# ruralhack-board.net
KiCad netlist of a schematic drawn in EAGLE
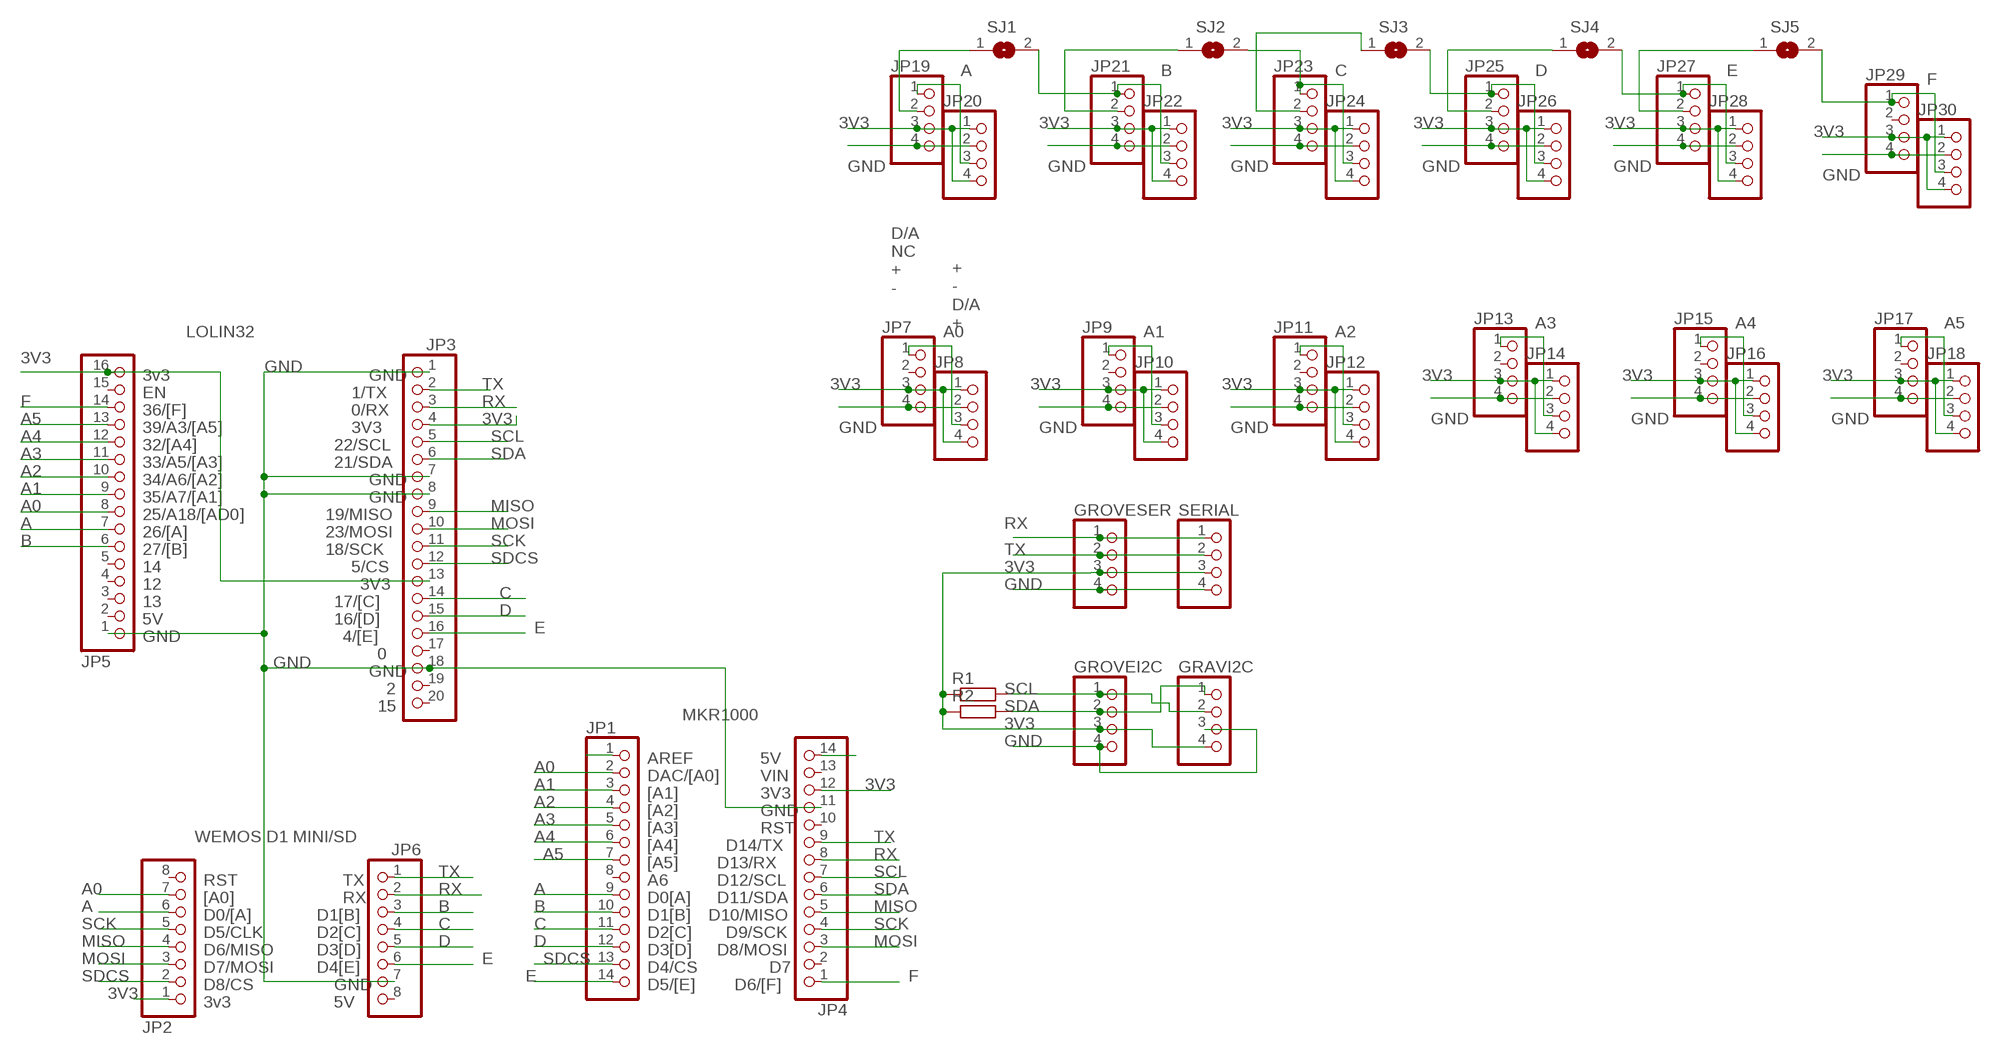
[diagram p0: schematic, sheet 1]

(export (version "E")
  (design (tool "Eeschema 10.0.6"))
  (components
    (comp (ref "GRAVI2C")
      (value "PINHD-1X4")
      (footprint "eagle-import:1X04")
      (libsource (lib "eagle-import") (part "PINHD-1X4"))
    )
    (comp (ref "GROVEI2C")
      (value "PINHD-1X4")
      (footprint "eagle-import:1X04")
      (libsource (lib "eagle-import") (part "PINHD-1X4"))
    )
    (comp (ref "GROVESER")
      (value "PINHD-1X4")
      (footprint "eagle-import:1X04")
      (libsource (lib "eagle-import") (part "PINHD-1X4"))
    )
    (comp (ref "JP1")
      (value "PINHD-1X14")
      (footprint "eagle-import:1X14")
      (libsource (lib "eagle-import") (part "PINHD-1X14"))
    )
    (comp (ref "JP2")
      (value "PINHD-1X8")
      (footprint "eagle-import:1X08")
      (libsource (lib "eagle-import") (part "PINHD-1X8"))
    )
    (comp (ref "JP3")
      (value "PINHD-1X20")
      (footprint "eagle-import:1X20")
      (libsource (lib "eagle-import") (part "PINHD-1X20"))
    )
    (comp (ref "JP4")
      (value "PINHD-1X14")
      (footprint "eagle-import:1X14")
      (libsource (lib "eagle-import") (part "PINHD-1X14"))
    )
    (comp (ref "JP5")
      (value "PINHD-1X16")
      (footprint "eagle-import:1X16")
      (libsource (lib "eagle-import") (part "PINHD-1X16"))
    )
    (comp (ref "JP6")
      (value "PINHD-1X8")
      (footprint "eagle-import:1X08")
      (libsource (lib "eagle-import") (part "PINHD-1X8"))
    )
    (comp (ref "JP7")
      (value "PINHD-1X4")
      (footprint "eagle-import:1X04")
      (libsource (lib "eagle-import") (part "PINHD-1X4"))
    )
    (comp (ref "JP8")
      (value "PINHD-1X4")
      (footprint "eagle-import:1X04")
      (libsource (lib "eagle-import") (part "PINHD-1X4"))
    )
    (comp (ref "JP9")
      (value "PINHD-1X4")
      (footprint "eagle-import:1X04")
      (libsource (lib "eagle-import") (part "PINHD-1X4"))
    )
    (comp (ref "JP10")
      (value "PINHD-1X4")
      (footprint "eagle-import:1X04")
      (libsource (lib "eagle-import") (part "PINHD-1X4"))
    )
    (comp (ref "JP11")
      (value "PINHD-1X4")
      (footprint "eagle-import:1X04")
      (libsource (lib "eagle-import") (part "PINHD-1X4"))
    )
    (comp (ref "JP12")
      (value "PINHD-1X4")
      (footprint "eagle-import:1X04")
      (libsource (lib "eagle-import") (part "PINHD-1X4"))
    )
    (comp (ref "JP13")
      (value "PINHD-1X4")
      (footprint "eagle-import:1X04")
      (libsource (lib "eagle-import") (part "PINHD-1X4"))
    )
    (comp (ref "JP14")
      (value "PINHD-1X4")
      (footprint "eagle-import:1X04")
      (libsource (lib "eagle-import") (part "PINHD-1X4"))
    )
    (comp (ref "JP15")
      (value "PINHD-1X4")
      (footprint "eagle-import:1X04")
      (libsource (lib "eagle-import") (part "PINHD-1X4"))
    )
    (comp (ref "JP16")
      (value "PINHD-1X4")
      (footprint "eagle-import:1X04")
      (libsource (lib "eagle-import") (part "PINHD-1X4"))
    )
    (comp (ref "JP17")
      (value "PINHD-1X4")
      (footprint "eagle-import:1X04")
      (libsource (lib "eagle-import") (part "PINHD-1X4"))
    )
    (comp (ref "JP18")
      (value "PINHD-1X4")
      (footprint "eagle-import:1X04")
      (libsource (lib "eagle-import") (part "PINHD-1X4"))
    )
    (comp (ref "JP19")
      (value "PINHD-1X4")
      (footprint "eagle-import:1X04")
      (libsource (lib "eagle-import") (part "PINHD-1X4"))
    )
    (comp (ref "JP20")
      (value "PINHD-1X4")
      (footprint "eagle-import:1X04")
      (libsource (lib "eagle-import") (part "PINHD-1X4"))
    )
    (comp (ref "JP21")
      (value "PINHD-1X4")
      (footprint "eagle-import:1X04")
      (libsource (lib "eagle-import") (part "PINHD-1X4"))
    )
    (comp (ref "JP22")
      (value "PINHD-1X4")
      (footprint "eagle-import:1X04")
      (libsource (lib "eagle-import") (part "PINHD-1X4"))
    )
    (comp (ref "JP23")
      (value "PINHD-1X4")
      (footprint "eagle-import:1X04")
      (libsource (lib "eagle-import") (part "PINHD-1X4"))
    )
    (comp (ref "JP24")
      (value "PINHD-1X4")
      (footprint "eagle-import:1X04")
      (libsource (lib "eagle-import") (part "PINHD-1X4"))
    )
    (comp (ref "JP25")
      (value "PINHD-1X4")
      (footprint "eagle-import:1X04")
      (libsource (lib "eagle-import") (part "PINHD-1X4"))
    )
    (comp (ref "JP26")
      (value "PINHD-1X4")
      (footprint "eagle-import:1X04")
      (libsource (lib "eagle-import") (part "PINHD-1X4"))
    )
    (comp (ref "JP27")
      (value "PINHD-1X4")
      (footprint "eagle-import:1X04")
      (libsource (lib "eagle-import") (part "PINHD-1X4"))
    )
    (comp (ref "JP28")
      (value "PINHD-1X4")
      (footprint "eagle-import:1X04")
      (libsource (lib "eagle-import") (part "PINHD-1X4"))
    )
    (comp (ref "JP29")
      (value "PINHD-1X4")
      (footprint "eagle-import:1X04")
      (libsource (lib "eagle-import") (part "PINHD-1X4"))
    )
    (comp (ref "JP30")
      (value "PINHD-1X4")
      (footprint "eagle-import:1X04")
      (libsource (lib "eagle-import") (part "PINHD-1X4"))
    )
    (comp (ref "R1")
      (value "R-EU_0204/7")
      (footprint "eagle-import:0204_7")
      (libsource (lib "eagle-import") (part "R-EU_0204/7"))
    )
    (comp (ref "R2")
      (value "R-EU_0204/7")
      (footprint "eagle-import:0204_7")
      (libsource (lib "eagle-import") (part "R-EU_0204/7"))
    )
    (comp (ref "SERIAL")
      (value "PINHD-1X4")
      (footprint "eagle-import:1X04")
      (libsource (lib "eagle-import") (part "PINHD-1X4"))
    )
    (comp (ref "SJ1")
      (value "SJW")
      (footprint "eagle-import:SJW")
      (libsource (lib "eagle-import") (part "SJW"))
    )
    (comp (ref "SJ2")
      (value "SJW")
      (footprint "eagle-import:SJW")
      (libsource (lib "eagle-import") (part "SJW"))
    )
    (comp (ref "SJ3")
      (value "SJW")
      (footprint "eagle-import:SJW")
      (libsource (lib "eagle-import") (part "SJW"))
    )
    (comp (ref "SJ4")
      (value "SJW")
      (footprint "eagle-import:SJW")
      (libsource (lib "eagle-import") (part "SJW"))
    )
    (comp (ref "SJ5")
      (value "SJW")
      (footprint "eagle-import:SJW")
      (libsource (lib "eagle-import") (part "SJW"))
    )
  )
  (nets
    (net (code "1") (name "/3V3") (class "Default")
      (node (ref "GRAVI2C") (pin "4") (pinfunction "4_4") (pintype "passive"))
      (node (ref "GROVEI2C") (pin "3") (pinfunction "3_3") (pintype "passive"))
      (node (ref "GROVESER") (pin "3") (pinfunction "3_3") (pintype "passive"))
      (node (ref "JP10") (pin "1") (pinfunction "1_1") (pintype "passive"))
      (node (ref "JP10") (pin "4") (pinfunction "4_4") (pintype "passive"))
      (node (ref "JP11") (pin "3") (pinfunction "3_3") (pintype "passive"))
      (node (ref "JP12") (pin "1") (pinfunction "1_1") (pintype "passive"))
      (node (ref "JP12") (pin "4") (pinfunction "4_4") (pintype "passive"))
      (node (ref "JP13") (pin "3") (pinfunction "3_3") (pintype "passive"))
      (node (ref "JP14") (pin "1") (pinfunction "1_1") (pintype "passive"))
      (node (ref "JP14") (pin "4") (pinfunction "4_4") (pintype "passive"))
      (node (ref "JP15") (pin "3") (pinfunction "3_3") (pintype "passive"))
      (node (ref "JP16") (pin "1") (pinfunction "1_1") (pintype "passive"))
      (node (ref "JP16") (pin "4") (pinfunction "4_4") (pintype "passive"))
      (node (ref "JP17") (pin "3") (pinfunction "3_3") (pintype "passive"))
      (node (ref "JP18") (pin "1") (pinfunction "1_1") (pintype "passive"))
      (node (ref "JP18") (pin "4") (pinfunction "4_4") (pintype "passive"))
      (node (ref "JP19") (pin "3") (pinfunction "3_3") (pintype "passive"))
      (node (ref "JP2") (pin "1") (pinfunction "1_1") (pintype "passive"))
      (node (ref "JP20") (pin "1") (pinfunction "1_1") (pintype "passive"))
      (node (ref "JP20") (pin "4") (pinfunction "4_4") (pintype "passive"))
      (node (ref "JP21") (pin "3") (pinfunction "3_3") (pintype "passive"))
      (node (ref "JP22") (pin "1") (pinfunction "1_1") (pintype "passive"))
      (node (ref "JP22") (pin "4") (pinfunction "4_4") (pintype "passive"))
      (node (ref "JP23") (pin "3") (pinfunction "3_3") (pintype "passive"))
      (node (ref "JP24") (pin "1") (pinfunction "1_1") (pintype "passive"))
      (node (ref "JP24") (pin "4") (pinfunction "4_4") (pintype "passive"))
      (node (ref "JP25") (pin "3") (pinfunction "3_3") (pintype "passive"))
      (node (ref "JP26") (pin "1") (pinfunction "1_1") (pintype "passive"))
      (node (ref "JP26") (pin "4") (pinfunction "4_4") (pintype "passive"))
      (node (ref "JP27") (pin "3") (pinfunction "3_3") (pintype "passive"))
      (node (ref "JP28") (pin "1") (pinfunction "1_1") (pintype "passive"))
      (node (ref "JP28") (pin "4") (pinfunction "4_4") (pintype "passive"))
      (node (ref "JP29") (pin "3") (pinfunction "3_3") (pintype "passive"))
      (node (ref "JP3") (pin "13") (pinfunction "13_13") (pintype "passive"))
      (node (ref "JP3") (pin "4") (pinfunction "4_4") (pintype "passive"))
      (node (ref "JP30") (pin "1") (pinfunction "1_1") (pintype "passive"))
      (node (ref "JP30") (pin "4") (pinfunction "4_4") (pintype "passive"))
      (node (ref "JP4") (pin "12") (pinfunction "12_12") (pintype "passive"))
      (node (ref "JP5") (pin "16") (pinfunction "16_16") (pintype "passive"))
      (node (ref "JP7") (pin "3") (pinfunction "3_3") (pintype "passive"))
      (node (ref "JP8") (pin "1") (pinfunction "1_1") (pintype "passive"))
      (node (ref "JP8") (pin "4") (pinfunction "4_4") (pintype "passive"))
      (node (ref "JP9") (pin "3") (pinfunction "3_3") (pintype "passive"))
      (node (ref "R1") (pin "1") (pinfunction "1_1") (pintype "passive"))
      (node (ref "R2") (pin "1") (pinfunction "1_1") (pintype "passive"))
      (node (ref "SERIAL") (pin "3") (pinfunction "3_3") (pintype "passive"))
    )
    (net (code "2") (name "/A") (class "Default")
      (node (ref "JP1") (pin "9") (pinfunction "9_9") (pintype "passive"))
      (node (ref "JP19") (pin "1") (pinfunction "1_1") (pintype "passive"))
      (node (ref "JP2") (pin "6") (pinfunction "6_6") (pintype "passive"))
      (node (ref "JP20") (pin "3") (pinfunction "3_3") (pintype "passive"))
      (node (ref "JP5") (pin "7") (pinfunction "7_7") (pintype "passive"))
    )
    (net (code "3") (name "/A0") (class "Default")
      (node (ref "JP1") (pin "2") (pinfunction "2_2") (pintype "passive"))
      (node (ref "JP2") (pin "7") (pinfunction "7_7") (pintype "passive"))
      (node (ref "JP5") (pin "8") (pinfunction "8_8") (pintype "passive"))
      (node (ref "JP7") (pin "1") (pinfunction "1_1") (pintype "passive"))
      (node (ref "JP8") (pin "3") (pinfunction "3_3") (pintype "passive"))
    )
    (net (code "4") (name "/A1") (class "Default")
      (node (ref "JP1") (pin "3") (pinfunction "3_3") (pintype "passive"))
      (node (ref "JP10") (pin "3") (pinfunction "3_3") (pintype "passive"))
      (node (ref "JP5") (pin "9") (pinfunction "9_9") (pintype "passive"))
      (node (ref "JP9") (pin "1") (pinfunction "1_1") (pintype "passive"))
    )
    (net (code "5") (name "/A2") (class "Default")
      (node (ref "JP1") (pin "4") (pinfunction "4_4") (pintype "passive"))
      (node (ref "JP11") (pin "1") (pinfunction "1_1") (pintype "passive"))
      (node (ref "JP12") (pin "3") (pinfunction "3_3") (pintype "passive"))
      (node (ref "JP5") (pin "10") (pinfunction "10_10") (pintype "passive"))
    )
    (net (code "6") (name "/A3") (class "Default")
      (node (ref "JP1") (pin "5") (pinfunction "5_5") (pintype "passive"))
      (node (ref "JP13") (pin "1") (pinfunction "1_1") (pintype "passive"))
      (node (ref "JP14") (pin "3") (pinfunction "3_3") (pintype "passive"))
      (node (ref "JP5") (pin "11") (pinfunction "11_11") (pintype "passive"))
    )
    (net (code "7") (name "/A4") (class "Default")
      (node (ref "JP1") (pin "6") (pinfunction "6_6") (pintype "passive"))
      (node (ref "JP15") (pin "1") (pinfunction "1_1") (pintype "passive"))
      (node (ref "JP16") (pin "3") (pinfunction "3_3") (pintype "passive"))
      (node (ref "JP5") (pin "12") (pinfunction "12_12") (pintype "passive"))
    )
    (net (code "8") (name "/A5") (class "Default")
      (node (ref "JP1") (pin "7") (pinfunction "7_7") (pintype "passive"))
      (node (ref "JP17") (pin "1") (pinfunction "1_1") (pintype "passive"))
      (node (ref "JP18") (pin "3") (pinfunction "3_3") (pintype "passive"))
      (node (ref "JP5") (pin "13") (pinfunction "13_13") (pintype "passive"))
    )
    (net (code "9") (name "/B") (class "Default")
      (node (ref "JP1") (pin "10") (pinfunction "10_10") (pintype "passive"))
      (node (ref "JP21") (pin "1") (pinfunction "1_1") (pintype "passive"))
      (node (ref "JP22") (pin "3") (pinfunction "3_3") (pintype "passive"))
      (node (ref "JP5") (pin "6") (pinfunction "6_6") (pintype "passive"))
      (node (ref "JP6") (pin "3") (pinfunction "3_3") (pintype "passive"))
      (node (ref "SJ1") (pin "2") (pinfunction "2_2") (pintype "passive"))
    )
    (net (code "10") (name "/C") (class "Default")
      (node (ref "JP1") (pin "11") (pinfunction "11_11") (pintype "passive"))
      (node (ref "JP23") (pin "1") (pinfunction "1_1") (pintype "passive"))
      (node (ref "JP24") (pin "3") (pinfunction "3_3") (pintype "passive"))
      (node (ref "JP3") (pin "14") (pinfunction "14_14") (pintype "passive"))
      (node (ref "JP6") (pin "4") (pinfunction "4_4") (pintype "passive"))
      (node (ref "SJ2") (pin "2") (pinfunction "2_2") (pintype "passive"))
    )
    (net (code "11") (name "/D") (class "Default")
      (node (ref "JP1") (pin "12") (pinfunction "12_12") (pintype "passive"))
      (node (ref "JP25") (pin "1") (pinfunction "1_1") (pintype "passive"))
      (node (ref "JP26") (pin "3") (pinfunction "3_3") (pintype "passive"))
      (node (ref "JP3") (pin "15") (pinfunction "15_15") (pintype "passive"))
      (node (ref "JP6") (pin "5") (pinfunction "5_5") (pintype "passive"))
      (node (ref "SJ3") (pin "2") (pinfunction "2_2") (pintype "passive"))
    )
    (net (code "12") (name "/E") (class "Default")
      (node (ref "JP1") (pin "14") (pinfunction "14_14") (pintype "passive"))
      (node (ref "JP27") (pin "1") (pinfunction "1_1") (pintype "passive"))
      (node (ref "JP28") (pin "3") (pinfunction "3_3") (pintype "passive"))
      (node (ref "JP3") (pin "16") (pinfunction "16_16") (pintype "passive"))
      (node (ref "JP6") (pin "6") (pinfunction "6_6") (pintype "passive"))
      (node (ref "SJ4") (pin "2") (pinfunction "2_2") (pintype "passive"))
    )
    (net (code "13") (name "/F") (class "Default")
      (node (ref "JP29") (pin "1") (pinfunction "1_1") (pintype "passive"))
      (node (ref "JP30") (pin "3") (pinfunction "3_3") (pintype "passive"))
      (node (ref "JP4") (pin "1") (pinfunction "1_1") (pintype "passive"))
      (node (ref "JP5") (pin "14") (pinfunction "14_14") (pintype "passive"))
      (node (ref "SJ5") (pin "2") (pinfunction "2_2") (pintype "passive"))
    )
    (net (code "14") (name "/GND") (class "Default")
      (node (ref "GRAVI2C") (pin "3") (pinfunction "3_3") (pintype "passive"))
      (node (ref "GROVEI2C") (pin "4") (pinfunction "4_4") (pintype "passive"))
      (node (ref "GROVESER") (pin "4") (pinfunction "4_4") (pintype "passive"))
      (node (ref "JP10") (pin "2") (pinfunction "2_2") (pintype "passive"))
      (node (ref "JP11") (pin "4") (pinfunction "4_4") (pintype "passive"))
      (node (ref "JP12") (pin "2") (pinfunction "2_2") (pintype "passive"))
      (node (ref "JP13") (pin "4") (pinfunction "4_4") (pintype "passive"))
      (node (ref "JP14") (pin "2") (pinfunction "2_2") (pintype "passive"))
      (node (ref "JP15") (pin "4") (pinfunction "4_4") (pintype "passive"))
      (node (ref "JP16") (pin "2") (pinfunction "2_2") (pintype "passive"))
      (node (ref "JP17") (pin "4") (pinfunction "4_4") (pintype "passive"))
      (node (ref "JP18") (pin "2") (pinfunction "2_2") (pintype "passive"))
      (node (ref "JP19") (pin "4") (pinfunction "4_4") (pintype "passive"))
      (node (ref "JP20") (pin "2") (pinfunction "2_2") (pintype "passive"))
      (node (ref "JP21") (pin "4") (pinfunction "4_4") (pintype "passive"))
      (node (ref "JP22") (pin "2") (pinfunction "2_2") (pintype "passive"))
      (node (ref "JP23") (pin "4") (pinfunction "4_4") (pintype "passive"))
      (node (ref "JP24") (pin "2") (pinfunction "2_2") (pintype "passive"))
      (node (ref "JP25") (pin "4") (pinfunction "4_4") (pintype "passive"))
      (node (ref "JP26") (pin "2") (pinfunction "2_2") (pintype "passive"))
      (node (ref "JP27") (pin "4") (pinfunction "4_4") (pintype "passive"))
      (node (ref "JP28") (pin "2") (pinfunction "2_2") (pintype "passive"))
      (node (ref "JP29") (pin "4") (pinfunction "4_4") (pintype "passive"))
      (node (ref "JP3") (pin "1") (pinfunction "1_1") (pintype "passive"))
      (node (ref "JP3") (pin "18") (pinfunction "18_18") (pintype "passive"))
      (node (ref "JP3") (pin "7") (pinfunction "7_7") (pintype "passive"))
      (node (ref "JP3") (pin "8") (pinfunction "8_8") (pintype "passive"))
      (node (ref "JP30") (pin "2") (pinfunction "2_2") (pintype "passive"))
      (node (ref "JP4") (pin "11") (pinfunction "11_11") (pintype "passive"))
      (node (ref "JP5") (pin "1") (pinfunction "1_1") (pintype "passive"))
      (node (ref "JP6") (pin "7") (pinfunction "7_7") (pintype "passive"))
      (node (ref "JP7") (pin "4") (pinfunction "4_4") (pintype "passive"))
      (node (ref "JP8") (pin "2") (pinfunction "2_2") (pintype "passive"))
      (node (ref "JP9") (pin "4") (pinfunction "4_4") (pintype "passive"))
      (node (ref "SERIAL") (pin "4") (pinfunction "4_4") (pintype "passive"))
    )
    (net (code "15") (name "/MISO") (class "Default")
      (node (ref "JP2") (pin "4") (pinfunction "4_4") (pintype "passive"))
      (node (ref "JP3") (pin "9") (pinfunction "9_9") (pintype "passive"))
      (node (ref "JP4") (pin "5") (pinfunction "5_5") (pintype "passive"))
    )
    (net (code "16") (name "/MOSI") (class "Default")
      (node (ref "JP2") (pin "3") (pinfunction "3_3") (pintype "passive"))
      (node (ref "JP3") (pin "10") (pinfunction "10_10") (pintype "passive"))
      (node (ref "JP4") (pin "3") (pinfunction "3_3") (pintype "passive"))
    )
    (net (code "17") (name "/RX") (class "Default")
      (node (ref "GROVESER") (pin "1") (pinfunction "1_1") (pintype "passive"))
      (node (ref "JP3") (pin "3") (pinfunction "3_3") (pintype "passive"))
      (node (ref "JP4") (pin "8") (pinfunction "8_8") (pintype "passive"))
      (node (ref "JP6") (pin "2") (pinfunction "2_2") (pintype "passive"))
      (node (ref "SERIAL") (pin "1") (pinfunction "1_1") (pintype "passive"))
    )
    (net (code "18") (name "/SCK") (class "Default")
      (node (ref "JP2") (pin "5") (pinfunction "5_5") (pintype "passive"))
      (node (ref "JP3") (pin "11") (pinfunction "11_11") (pintype "passive"))
      (node (ref "JP4") (pin "4") (pinfunction "4_4") (pintype "passive"))
    )
    (net (code "19") (name "/SCL") (class "Default")
      (node (ref "GRAVI2C") (pin "2") (pinfunction "2_2") (pintype "passive"))
      (node (ref "GROVEI2C") (pin "1") (pinfunction "1_1") (pintype "passive"))
      (node (ref "JP3") (pin "5") (pinfunction "5_5") (pintype "passive"))
      (node (ref "JP4") (pin "7") (pinfunction "7_7") (pintype "passive"))
      (node (ref "R1") (pin "2") (pinfunction "2_2") (pintype "passive"))
    )
    (net (code "20") (name "/SDA") (class "Default")
      (node (ref "GRAVI2C") (pin "1") (pinfunction "1_1") (pintype "passive"))
      (node (ref "GROVEI2C") (pin "2") (pinfunction "2_2") (pintype "passive"))
      (node (ref "JP3") (pin "6") (pinfunction "6_6") (pintype "passive"))
      (node (ref "JP4") (pin "6") (pinfunction "6_6") (pintype "passive"))
      (node (ref "R2") (pin "2") (pinfunction "2_2") (pintype "passive"))
    )
    (net (code "21") (name "/SDCS") (class "Default")
      (node (ref "JP1") (pin "13") (pinfunction "13_13") (pintype "passive"))
      (node (ref "JP2") (pin "2") (pinfunction "2_2") (pintype "passive"))
      (node (ref "JP3") (pin "12") (pinfunction "12_12") (pintype "passive"))
    )
    (net (code "22") (name "/TX") (class "Default")
      (node (ref "GROVESER") (pin "2") (pinfunction "2_2") (pintype "passive"))
      (node (ref "JP3") (pin "2") (pinfunction "2_2") (pintype "passive"))
      (node (ref "JP4") (pin "9") (pinfunction "9_9") (pintype "passive"))
      (node (ref "JP6") (pin "1") (pinfunction "1_1") (pintype "passive"))
      (node (ref "SERIAL") (pin "2") (pinfunction "2_2") (pintype "passive"))
    )
    (net (code "23") (name "Net-(JP19-Pad2)") (class "Default")
      (node (ref "JP19") (pin "2") (pinfunction "2_2") (pintype "passive"))
      (node (ref "SJ1") (pin "1") (pinfunction "1_1") (pintype "passive"))
    )
    (net (code "24") (name "Net-(JP21-Pad2)") (class "Default")
      (node (ref "JP21") (pin "2") (pinfunction "2_2") (pintype "passive"))
      (node (ref "SJ2") (pin "1") (pinfunction "1_1") (pintype "passive"))
    )
    (net (code "25") (name "Net-(JP23-Pad2)") (class "Default")
      (node (ref "JP23") (pin "2") (pinfunction "2_2") (pintype "passive"))
      (node (ref "SJ3") (pin "1") (pinfunction "1_1") (pintype "passive"))
    )
    (net (code "26") (name "Net-(JP25-Pad2)") (class "Default")
      (node (ref "JP25") (pin "2") (pinfunction "2_2") (pintype "passive"))
      (node (ref "SJ4") (pin "1") (pinfunction "1_1") (pintype "passive"))
    )
    (net (code "27") (name "Net-(JP27-Pad2)") (class "Default")
      (node (ref "JP27") (pin "2") (pinfunction "2_2") (pintype "passive"))
      (node (ref "SJ5") (pin "1") (pinfunction "1_1") (pintype "passive"))
    )
    (net (code "28") (name "unconnected-(JP1-Pad1)") (class "Default")
      (node (ref "JP1") (pin "1") (pinfunction "1_1") (pintype "passive"))
    )
    (net (code "29") (name "unconnected-(JP1-Pad8)") (class "Default")
      (node (ref "JP1") (pin "8") (pinfunction "8_8") (pintype "passive"))
    )
    (net (code "30") (name "unconnected-(JP2-Pad8)") (class "Default")
      (node (ref "JP2") (pin "8") (pinfunction "8_8") (pintype "passive"))
    )
    (net (code "31") (name "unconnected-(JP3-Pad17)") (class "Default")
      (node (ref "JP3") (pin "17") (pinfunction "17_17") (pintype "passive"))
    )
    (net (code "32") (name "unconnected-(JP3-Pad19)") (class "Default")
      (node (ref "JP3") (pin "19") (pinfunction "19_19") (pintype "passive"))
    )
    (net (code "33") (name "unconnected-(JP3-Pad20)") (class "Default")
      (node (ref "JP3") (pin "20") (pinfunction "20_20") (pintype "passive"))
    )
    (net (code "34") (name "unconnected-(JP4-Pad2)") (class "Default")
      (node (ref "JP4") (pin "2") (pinfunction "2_2") (pintype "passive"))
    )
    (net (code "35") (name "unconnected-(JP4-Pad10)") (class "Default")
      (node (ref "JP4") (pin "10") (pinfunction "10_10") (pintype "passive"))
    )
    (net (code "36") (name "unconnected-(JP4-Pad13)") (class "Default")
      (node (ref "JP4") (pin "13") (pinfunction "13_13") (pintype "passive"))
    )
    (net (code "37") (name "unconnected-(JP4-Pad14)") (class "Default")
      (node (ref "JP4") (pin "14") (pinfunction "14_14") (pintype "passive"))
    )
    (net (code "38") (name "unconnected-(JP5-Pad2)") (class "Default")
      (node (ref "JP5") (pin "2") (pinfunction "2_2") (pintype "passive"))
    )
    (net (code "39") (name "unconnected-(JP5-Pad3)") (class "Default")
      (node (ref "JP5") (pin "3") (pinfunction "3_3") (pintype "passive"))
    )
    (net (code "40") (name "unconnected-(JP5-Pad4)") (class "Default")
      (node (ref "JP5") (pin "4") (pinfunction "4_4") (pintype "passive"))
    )
    (net (code "41") (name "unconnected-(JP5-Pad5)") (class "Default")
      (node (ref "JP5") (pin "5") (pinfunction "5_5") (pintype "passive"))
    )
    (net (code "42") (name "unconnected-(JP5-Pad15)") (class "Default")
      (node (ref "JP5") (pin "15") (pinfunction "15_15") (pintype "passive"))
    )
    (net (code "43") (name "unconnected-(JP6-Pad8)") (class "Default")
      (node (ref "JP6") (pin "8") (pinfunction "8_8") (pintype "passive"))
    )
    (net (code "44") (name "unconnected-(JP7-Pad2)") (class "Default")
      (node (ref "JP7") (pin "2") (pinfunction "2_2") (pintype "passive"))
    )
    (net (code "45") (name "unconnected-(JP9-Pad2)") (class "Default")
      (node (ref "JP9") (pin "2") (pinfunction "2_2") (pintype "passive"))
    )
    (net (code "46") (name "unconnected-(JP11-Pad2)") (class "Default")
      (node (ref "JP11") (pin "2") (pinfunction "2_2") (pintype "passive"))
    )
    (net (code "47") (name "unconnected-(JP13-Pad2)") (class "Default")
      (node (ref "JP13") (pin "2") (pinfunction "2_2") (pintype "passive"))
    )
    (net (code "48") (name "unconnected-(JP15-Pad2)") (class "Default")
      (node (ref "JP15") (pin "2") (pinfunction "2_2") (pintype "passive"))
    )
    (net (code "49") (name "unconnected-(JP17-Pad2)") (class "Default")
      (node (ref "JP17") (pin "2") (pinfunction "2_2") (pintype "passive"))
    )
    (net (code "50") (name "unconnected-(JP29-Pad2)") (class "Default")
      (node (ref "JP29") (pin "2") (pinfunction "2_2") (pintype "passive"))
    )
  )
)
